# 02_MCU.net
KiCad netlist of a schematic drawn in Altium Designer
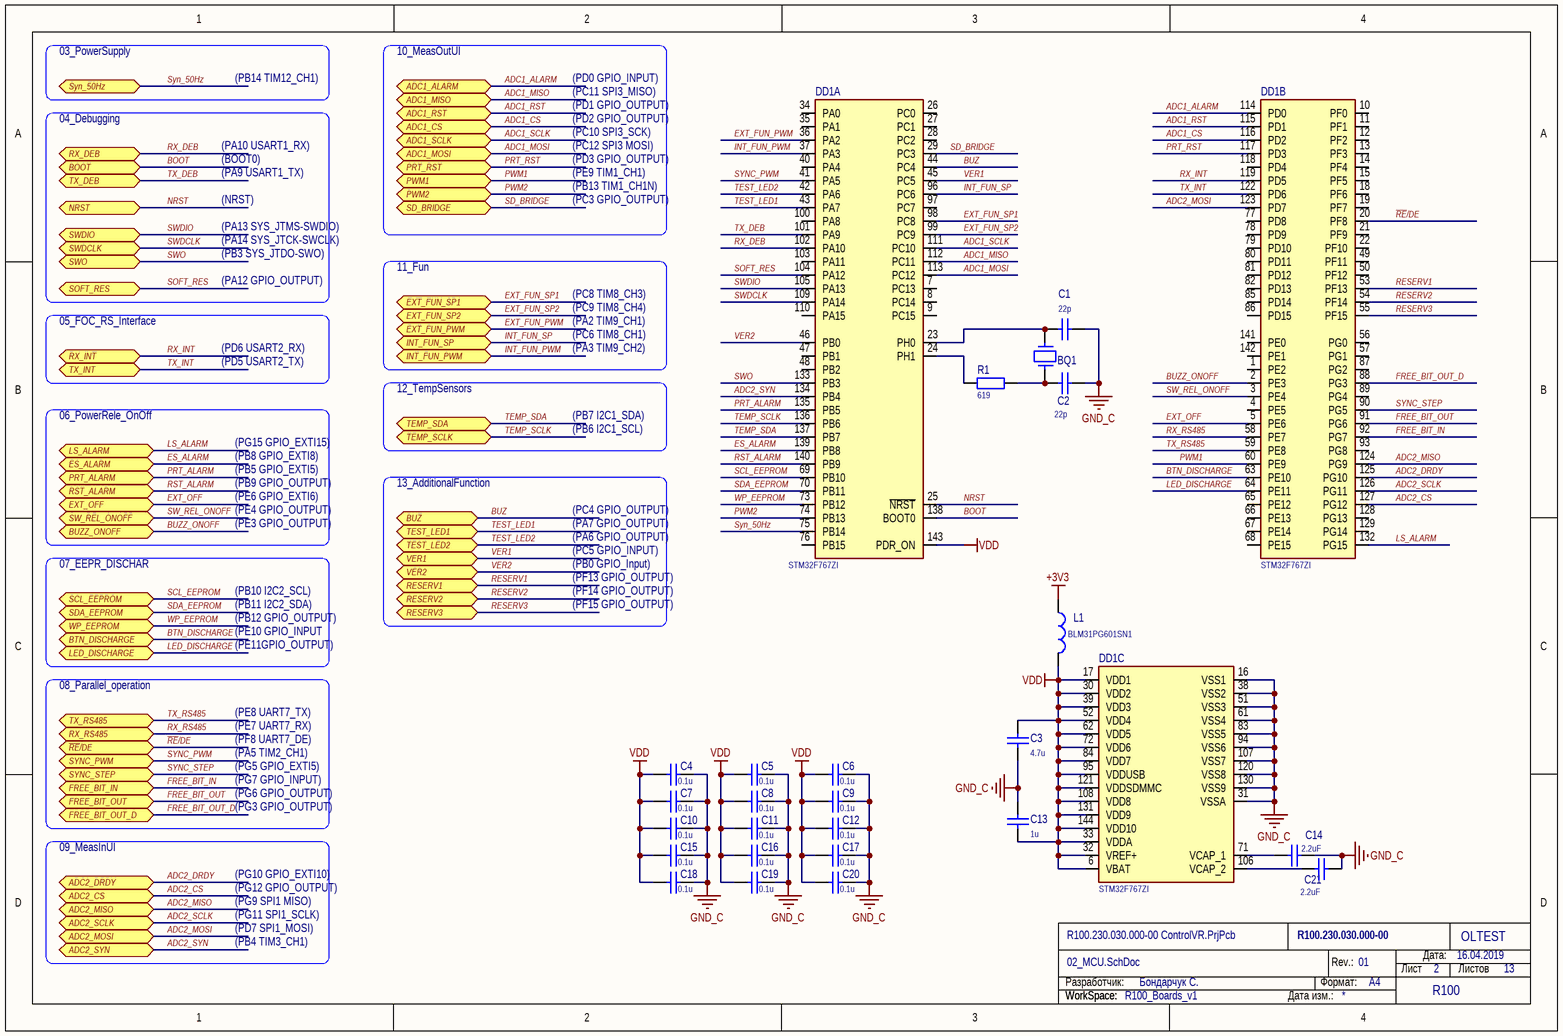
[diagram p0: 02_MCU.SchDoc]

(export (version "E")
  (design (tool "Eeschema 10.0.6"))
  (components
    (comp (ref "BQ1")
      (value "12MHz")
      (footprint "mainLib:DFN390P500X135-2N")
      (description "12MHz Quartz Crystal 7A")
      (fields (field (name "PARTNUMBER") "7A-12.000MAAJ-T") (field (name "MANUFACTURER") "TXC"))
      (libsource (lib "mainLib") (part "7A-12.000MAAJ-T"))
    )
    (comp (ref "C1")
      (value "22р")
      (footprint "mainLib:SMD_C_0603")
      (description "SMD C 0603 MURATA 50V 5% C0G")
      (fields (field (name "PARTNUMBER") "GRM1885C1H220JA01") (field (name "MANUFACTURER") "MURATA"))
      (libsource (lib "mainRCLib") (part "C0603 22p 50V 5%"))
    )
    (comp (ref "C2")
      (value "22р")
      (footprint "mainLib:SMD_C_0603")
      (description "SMD C 0603 MURATA 50V 5% C0G")
      (fields (field (name "PARTNUMBER") "GRM1885C1H220JA01") (field (name "MANUFACTURER") "MURATA"))
      (libsource (lib "mainRCLib") (part "C0603 22p 50V 5%"))
    )
    (comp (ref "C3")
      (value "4.7u")
      (footprint "mainLib:SMD_C_0805")
      (description "SMD C 0805 MURATA 50V 5% NP0")
      (fields (field (name "PARTNUMBER") "GRM21BR61E475M") (field (name "MANUFACTURER") "MURATA"))
      (libsource (lib "mainRCLib") (part "C0805 4.7u 25V 20%  X5R"))
    )
    (comp (ref "C4")
      (value "0.1u")
      (footprint "mainLib:SMD_C_0603")
      (description "SMD C 0603 MURATA 50V 10% X7R")
      (fields (field (name "PARTNUMBER") "GRM188R71H104K") (field (name "MANUFACTURER") "MURATA"))
      (libsource (lib "mainRCLib") (part "C0603 0.1u 50V 10%"))
    )
    (comp (ref "C5")
      (value "0.1u")
      (footprint "mainLib:SMD_C_0603")
      (description "SMD C 0603 MURATA 50V 10% X7R")
      (fields (field (name "PARTNUMBER") "GRM188R71H104K") (field (name "MANUFACTURER") "MURATA"))
      (libsource (lib "mainRCLib") (part "C0603 0.1u 50V 10%"))
    )
    (comp (ref "C6")
      (value "0.1u")
      (footprint "mainLib:SMD_C_0603")
      (description "SMD C 0603 MURATA 50V 10% X7R")
      (fields (field (name "PARTNUMBER") "GRM188R71H104K") (field (name "MANUFACTURER") "MURATA"))
      (libsource (lib "mainRCLib") (part "C0603 0.1u 50V 10%"))
    )
    (comp (ref "C7")
      (value "0.1u")
      (footprint "mainLib:SMD_C_0603")
      (description "SMD C 0603 MURATA 50V 10% X7R")
      (fields (field (name "PARTNUMBER") "GRM188R71H104K") (field (name "MANUFACTURER") "MURATA"))
      (libsource (lib "mainRCLib") (part "C0603 0.1u 50V 10%"))
    )
    (comp (ref "C8")
      (value "0.1u")
      (footprint "mainLib:SMD_C_0603")
      (description "SMD C 0603 MURATA 50V 10% X7R")
      (fields (field (name "PARTNUMBER") "GRM188R71H104K") (field (name "MANUFACTURER") "MURATA"))
      (libsource (lib "mainRCLib") (part "C0603 0.1u 50V 10%"))
    )
    (comp (ref "C9")
      (value "0.1u")
      (footprint "mainLib:SMD_C_0603")
      (description "SMD C 0603 MURATA 50V 10% X7R")
      (fields (field (name "PARTNUMBER") "GRM188R71H104K") (field (name "MANUFACTURER") "MURATA"))
      (libsource (lib "mainRCLib") (part "C0603 0.1u 50V 10%"))
    )
    (comp (ref "C10")
      (value "0.1u")
      (footprint "mainLib:SMD_C_0603")
      (description "SMD C 0603 MURATA 50V 10% X7R")
      (fields (field (name "PARTNUMBER") "GRM188R71H104K") (field (name "MANUFACTURER") "MURATA"))
      (libsource (lib "mainRCLib") (part "C0603 0.1u 50V 10%"))
    )
    (comp (ref "C11")
      (value "0.1u")
      (footprint "mainLib:SMD_C_0603")
      (description "SMD C 0603 MURATA 50V 10% X7R")
      (fields (field (name "PARTNUMBER") "GRM188R71H104K") (field (name "MANUFACTURER") "MURATA"))
      (libsource (lib "mainRCLib") (part "C0603 0.1u 50V 10%"))
    )
    (comp (ref "C12")
      (value "0.1u")
      (footprint "mainLib:SMD_C_0603")
      (description "SMD C 0603 MURATA 50V 10% X7R")
      (fields (field (name "PARTNUMBER") "GRM188R71H104K") (field (name "MANUFACTURER") "MURATA"))
      (libsource (lib "mainRCLib") (part "C0603 0.1u 50V 10%"))
    )
    (comp (ref "C13")
      (value "1u")
      (footprint "mainLib:SMD_C_0603")
      (description "SMD C 0603 MURATA 25V 10% X7R")
      (fields (field (name "PARTNUMBER") "GRM188R71E105KA12") (field (name "MANUFACTURER") "MURATA"))
      (libsource (lib "mainRCLib") (part "C0603 1uF 25V 10%"))
    )
    (comp (ref "C14")
      (value "2.2uF")
      (footprint "mainLib:SMD_C_0805")
      (description "SMD C 0805 MURATA 25V 10% X7R")
      (fields (field (name "PARTNUMBER") "GRM21BR61H225M") (field (name "MANUFACTURER") "MURATA"))
      (libsource (lib "mainRCLib") (part "C0805 2.2u 25V 10% X7R"))
    )
    (comp (ref "C15")
      (value "0.1u")
      (footprint "mainLib:SMD_C_0603")
      (description "SMD C 0603 MURATA 50V 10% X7R")
      (fields (field (name "PARTNUMBER") "GRM188R71H104K") (field (name "MANUFACTURER") "MURATA"))
      (libsource (lib "mainRCLib") (part "C0603 0.1u 50V 10%"))
    )
    (comp (ref "C16")
      (value "0.1u")
      (footprint "mainLib:SMD_C_0603")
      (description "SMD C 0603 MURATA 50V 10% X7R")
      (fields (field (name "PARTNUMBER") "GRM188R71H104K") (field (name "MANUFACTURER") "MURATA"))
      (libsource (lib "mainRCLib") (part "C0603 0.1u 50V 10%"))
    )
    (comp (ref "C17")
      (value "0.1u")
      (footprint "mainLib:SMD_C_0603")
      (description "SMD C 0603 MURATA 50V 10% X7R")
      (fields (field (name "PARTNUMBER") "GRM188R71H104K") (field (name "MANUFACTURER") "MURATA"))
      (libsource (lib "mainRCLib") (part "C0603 0.1u 50V 10%"))
    )
    (comp (ref "C18")
      (value "0.1u")
      (footprint "mainLib:SMD_C_0603")
      (description "SMD C 0603 MURATA 50V 10% X7R")
      (fields (field (name "PARTNUMBER") "GRM188R71H104K") (field (name "MANUFACTURER") "MURATA"))
      (libsource (lib "mainRCLib") (part "C0603 0.1u 50V 10%"))
    )
    (comp (ref "C19")
      (value "0.1u")
      (footprint "mainLib:SMD_C_0603")
      (description "SMD C 0603 MURATA 50V 10% X7R")
      (fields (field (name "PARTNUMBER") "GRM188R71H104K") (field (name "MANUFACTURER") "MURATA"))
      (libsource (lib "mainRCLib") (part "C0603 0.1u 50V 10%"))
    )
    (comp (ref "C20")
      (value "0.1u")
      (footprint "mainLib:SMD_C_0603")
      (description "SMD C 0603 MURATA 50V 10% X7R")
      (fields (field (name "PARTNUMBER") "GRM188R71H104K") (field (name "MANUFACTURER") "MURATA"))
      (libsource (lib "mainRCLib") (part "C0603 0.1u 50V 10%"))
    )
    (comp (ref "C21")
      (value "2.2uF")
      (footprint "mainLib:SMD_C_0805")
      (description "SMD C 0805 MURATA 25V 10% X7R")
      (fields (field (name "PARTNUMBER") "GRM21BR61H225M") (field (name "MANUFACTURER") "MURATA"))
      (libsource (lib "mainRCLib") (part "C0805 2.2u 25V 10% X7R"))
    )
    (comp (ref "DD1")
      (value "STM32F767ZI")
      (footprint "mainLib:SOT486-1_V")
      (description "32-bit ARM Cortex-M7 MCU+FPU")
      (libsource (lib "mainLib") (part "STM32F767ZI"))
    )
    (comp (ref "L1")
      (value "BLM31PG601SN1")
      (footprint "mainLib:SMD_L_1206")
      (description "600R 1.5A (100MHz)")
      (fields (field (name "MANUFACTURER") "TDK"))
      (libsource (lib "mainLib") (part "BLM31PG601SN1"))
    )
    (comp (ref "R1")
      (value "619")
      (footprint "mainLib:SMD_R_0603")
      (description "SMD 0603 VISHAY 0.1W 75V 1% 100ppm")
      (fields (field (name "PARTNUMBER") "CRCW0603619RFK") (field (name "MANUFACTURER") "VISHAY"))
      (libsource (lib "mainRCLib") (part "R0603 619 1%"))
    )
  )
  (nets
    (net (code "1") (name "+3V3") (class "Default")
      (node (ref "L1") (pin "1") (pinfunction "1_1") (pintype "passive"))
    )
    (net (code "2") (name "/ADC1_ALARM") (class "Default")
      (node (ref "DD1") (pin "114") (pinfunction "PD0_114") (pintype "passive"))
    )
    (net (code "3") (name "/ADC1_CS") (class "Default")
      (node (ref "DD1") (pin "116") (pinfunction "PD2_116") (pintype "passive"))
    )
    (net (code "4") (name "/ADC1_MISO") (class "Default")
      (node (ref "DD1") (pin "112") (pinfunction "PC11_112") (pintype "passive"))
    )
    (net (code "5") (name "/ADC1_MOSI") (class "Default")
      (node (ref "DD1") (pin "113") (pinfunction "PC12_113") (pintype "passive"))
    )
    (net (code "6") (name "/ADC1_RST") (class "Default")
      (node (ref "DD1") (pin "115") (pinfunction "PD1_115") (pintype "passive"))
    )
    (net (code "7") (name "/ADC1_SCLK") (class "Default")
      (node (ref "DD1") (pin "111") (pinfunction "PC10_111") (pintype "passive"))
    )
    (net (code "8") (name "/ADC2_CS") (class "Default")
      (node (ref "DD1") (pin "127") (pinfunction "PG12_127") (pintype "passive"))
    )
    (net (code "9") (name "/ADC2_DRDY") (class "Default")
      (node (ref "DD1") (pin "125") (pinfunction "PG10_125") (pintype "passive"))
    )
    (net (code "10") (name "/ADC2_MISO") (class "Default")
      (node (ref "DD1") (pin "124") (pinfunction "PG9_124") (pintype "passive"))
    )
    (net (code "11") (name "/ADC2_MOSI") (class "Default")
      (node (ref "DD1") (pin "123") (pinfunction "PD7_123") (pintype "passive"))
    )
    (net (code "12") (name "/ADC2_SCLK") (class "Default")
      (node (ref "DD1") (pin "126") (pinfunction "PG11_126") (pintype "passive"))
    )
    (net (code "13") (name "/ADC2_SYN") (class "Default")
      (node (ref "DD1") (pin "134") (pinfunction "PB4_134") (pintype "passive"))
    )
    (net (code "14") (name "/BOOT") (class "Default")
      (node (ref "DD1") (pin "138") (pinfunction "BOOT0_138") (pintype "passive"))
    )
    (net (code "15") (name "/BTN_DISCHARGE") (class "Default")
      (node (ref "DD1") (pin "63") (pinfunction "PE10_63") (pintype "passive"))
    )
    (net (code "16") (name "/BUZ") (class "Default")
      (node (ref "DD1") (pin "44") (pinfunction "PC4_44") (pintype "passive"))
    )
    (net (code "17") (name "/BUZZ_ONOFF") (class "Default")
      (node (ref "DD1") (pin "2") (pinfunction "PE3_2") (pintype "passive"))
    )
    (net (code "18") (name "/ES_ALARM") (class "Default")
      (node (ref "DD1") (pin "139") (pinfunction "PB8_139") (pintype "passive"))
    )
    (net (code "19") (name "/EXT_FUN_PWM") (class "Default")
      (node (ref "DD1") (pin "36") (pinfunction "PA2_36") (pintype "passive"))
    )
    (net (code "20") (name "/EXT_FUN_SP1") (class "Default")
      (node (ref "DD1") (pin "98") (pinfunction "PC8_98") (pintype "passive"))
    )
    (net (code "21") (name "/EXT_FUN_SP2") (class "Default")
      (node (ref "DD1") (pin "99") (pinfunction "PC9_99") (pintype "passive"))
    )
    (net (code "22") (name "/EXT_OFF") (class "Default")
      (node (ref "DD1") (pin "5") (pinfunction "PE6_5") (pintype "passive"))
    )
    (net (code "23") (name "/FREE_BIT_IN") (class "Default")
      (node (ref "DD1") (pin "92") (pinfunction "PG7_92") (pintype "passive"))
    )
    (net (code "24") (name "/FREE_BIT_OUT") (class "Default")
      (node (ref "DD1") (pin "91") (pinfunction "PG6_91") (pintype "passive"))
    )
    (net (code "25") (name "/FREE_BIT_OUT_D") (class "Default")
      (node (ref "DD1") (pin "88") (pinfunction "PG3_88") (pintype "passive"))
    )
    (net (code "26") (name "/INT_FUN_PWM") (class "Default")
      (node (ref "DD1") (pin "37") (pinfunction "PA3_37") (pintype "passive"))
    )
    (net (code "27") (name "/INT_FUN_SP") (class "Default")
      (node (ref "DD1") (pin "96") (pinfunction "PC6_96") (pintype "passive"))
    )
    (net (code "28") (name "/LED_DISCHARGE") (class "Default")
      (node (ref "DD1") (pin "64") (pinfunction "PE11_64") (pintype "passive"))
    )
    (net (code "29") (name "/LS_ALARM") (class "Default")
      (node (ref "DD1") (pin "132") (pinfunction "PG15_132") (pintype "passive"))
    )
    (net (code "30") (name "/NRST") (class "Default")
      (node (ref "DD1") (pin "25") (pinfunction "~{NRST}_25") (pintype "passive"))
    )
    (net (code "31") (name "/PRT_ALARM") (class "Default")
      (node (ref "DD1") (pin "135") (pinfunction "PB5_135") (pintype "passive"))
    )
    (net (code "32") (name "/PRT_RST") (class "Default")
      (node (ref "DD1") (pin "117") (pinfunction "PD3_117") (pintype "passive"))
    )
    (net (code "33") (name "/PWM1") (class "Default")
      (node (ref "DD1") (pin "60") (pinfunction "PE9_60") (pintype "passive"))
    )
    (net (code "34") (name "/PWM2") (class "Default")
      (node (ref "DD1") (pin "74") (pinfunction "PB13_74") (pintype "passive"))
    )
    (net (code "35") (name "/RESERV1") (class "Default")
      (node (ref "DD1") (pin "53") (pinfunction "PF13_53") (pintype "passive"))
    )
    (net (code "36") (name "/RESERV2") (class "Default")
      (node (ref "DD1") (pin "54") (pinfunction "PF14_54") (pintype "passive"))
    )
    (net (code "37") (name "/RESERV3") (class "Default")
      (node (ref "DD1") (pin "55") (pinfunction "PF15_55") (pintype "passive"))
    )
    (net (code "38") (name "/RST_ALARM") (class "Default")
      (node (ref "DD1") (pin "140") (pinfunction "PB9_140") (pintype "passive"))
    )
    (net (code "39") (name "/RX_DEB") (class "Default")
      (node (ref "DD1") (pin "102") (pinfunction "PA10_102") (pintype "passive"))
    )
    (net (code "40") (name "/RX_INT") (class "Default")
      (node (ref "DD1") (pin "119") (pinfunction "PD5_119") (pintype "passive"))
    )
    (net (code "41") (name "/RX_RS485") (class "Default")
      (node (ref "DD1") (pin "58") (pinfunction "PE7_58") (pintype "passive"))
    )
    (net (code "42") (name "/SCL_EEPROM") (class "Default")
      (node (ref "DD1") (pin "69") (pinfunction "PB10_69") (pintype "passive"))
    )
    (net (code "43") (name "/SDA_EEPROM") (class "Default")
      (node (ref "DD1") (pin "70") (pinfunction "PB11_70") (pintype "passive"))
    )
    (net (code "44") (name "/SD_BRIDGE") (class "Default")
      (node (ref "DD1") (pin "29") (pinfunction "PC3_29") (pintype "passive"))
    )
    (net (code "45") (name "/SOFT_RES") (class "Default")
      (node (ref "DD1") (pin "104") (pinfunction "PA12_104") (pintype "passive"))
    )
    (net (code "46") (name "/SWDCLK") (class "Default")
      (node (ref "DD1") (pin "109") (pinfunction "PA14_109") (pintype "passive"))
    )
    (net (code "47") (name "/SWDIO") (class "Default")
      (node (ref "DD1") (pin "105") (pinfunction "PA13_105") (pintype "passive"))
    )
    (net (code "48") (name "/SWO") (class "Default")
      (node (ref "DD1") (pin "133") (pinfunction "PB3_133") (pintype "passive"))
    )
    (net (code "49") (name "/SW_REL_ONOFF") (class "Default")
      (node (ref "DD1") (pin "3") (pinfunction "PE4_3") (pintype "passive"))
    )
    (net (code "50") (name "/SYNC_PWM") (class "Default")
      (node (ref "DD1") (pin "41") (pinfunction "PA5_41") (pintype "passive"))
    )
    (net (code "51") (name "/SYNC_STEP") (class "Default")
      (node (ref "DD1") (pin "90") (pinfunction "PG5_90") (pintype "passive"))
    )
    (net (code "52") (name "/Syn_50Hz") (class "Default")
      (node (ref "DD1") (pin "75") (pinfunction "PB14_75") (pintype "passive"))
    )
    (net (code "53") (name "/TEMP_SCLK") (class "Default")
      (node (ref "DD1") (pin "136") (pinfunction "PB6_136") (pintype "passive"))
    )
    (net (code "54") (name "/TEMP_SDA") (class "Default")
      (node (ref "DD1") (pin "137") (pinfunction "PB7_137") (pintype "passive"))
    )
    (net (code "55") (name "/TEST_LED1") (class "Default")
      (node (ref "DD1") (pin "43") (pinfunction "PA7_43") (pintype "passive"))
    )
    (net (code "56") (name "/TEST_LED2") (class "Default")
      (node (ref "DD1") (pin "42") (pinfunction "PA6_42") (pintype "passive"))
    )
    (net (code "57") (name "/TX_DEB") (class "Default")
      (node (ref "DD1") (pin "101") (pinfunction "PA9_101") (pintype "passive"))
    )
    (net (code "58") (name "/TX_INT") (class "Default")
      (node (ref "DD1") (pin "122") (pinfunction "PD6_122") (pintype "passive"))
    )
    (net (code "59") (name "/TX_RS485") (class "Default")
      (node (ref "DD1") (pin "59") (pinfunction "PE8_59") (pintype "passive"))
    )
    (net (code "60") (name "/VER1") (class "Default")
      (node (ref "DD1") (pin "45") (pinfunction "PC5_45") (pintype "passive"))
    )
    (net (code "61") (name "/VER2") (class "Default")
      (node (ref "DD1") (pin "46") (pinfunction "PB0_46") (pintype "passive"))
    )
    (net (code "62") (name "/WP_EEPROM") (class "Default")
      (node (ref "DD1") (pin "73") (pinfunction "PB12_73") (pintype "passive"))
    )
    (net (code "63") (name "/~{RE}{slash}DE") (class "Default")
      (node (ref "DD1") (pin "20") (pinfunction "PF8_20") (pintype "passive"))
    )
    (net (code "64") (name "GND_C") (class "Default")
      (node (ref "C1") (pin "2") (pinfunction "2_2") (pintype "passive"))
      (node (ref "C10") (pin "2") (pinfunction "2_2") (pintype "passive"))
      (node (ref "C11") (pin "2") (pinfunction "2_2") (pintype "passive"))
      (node (ref "C12") (pin "2") (pinfunction "2_2") (pintype "passive"))
      (node (ref "C13") (pin "2") (pinfunction "2_2") (pintype "passive"))
      (node (ref "C14") (pin "2") (pinfunction "2_2") (pintype "passive"))
      (node (ref "C15") (pin "2") (pinfunction "2_2") (pintype "passive"))
      (node (ref "C16") (pin "2") (pinfunction "2_2") (pintype "passive"))
      (node (ref "C17") (pin "2") (pinfunction "2_2") (pintype "passive"))
      (node (ref "C18") (pin "2") (pinfunction "2_2") (pintype "passive"))
      (node (ref "C19") (pin "2") (pinfunction "2_2") (pintype "passive"))
      (node (ref "C2") (pin "2") (pinfunction "2_2") (pintype "passive"))
      (node (ref "C20") (pin "2") (pinfunction "2_2") (pintype "passive"))
      (node (ref "C21") (pin "2") (pinfunction "2_2") (pintype "passive"))
      (node (ref "C3") (pin "1") (pinfunction "1_1") (pintype "passive"))
      (node (ref "C4") (pin "2") (pinfunction "2_2") (pintype "passive"))
      (node (ref "C5") (pin "2") (pinfunction "2_2") (pintype "passive"))
      (node (ref "C6") (pin "2") (pinfunction "2_2") (pintype "passive"))
      (node (ref "C7") (pin "2") (pinfunction "2_2") (pintype "passive"))
      (node (ref "C8") (pin "2") (pinfunction "2_2") (pintype "passive"))
      (node (ref "C9") (pin "2") (pinfunction "2_2") (pintype "passive"))
      (node (ref "DD1") (pin "107") (pinfunction "VSS7_107") (pintype "passive"))
      (node (ref "DD1") (pin "120") (pinfunction "VSS8_120") (pintype "passive"))
      (node (ref "DD1") (pin "130") (pinfunction "VSS9_130") (pintype "passive"))
      (node (ref "DD1") (pin "16") (pinfunction "VSS1_16") (pintype "passive"))
      (node (ref "DD1") (pin "31") (pinfunction "VSSA_31") (pintype "passive"))
      (node (ref "DD1") (pin "38") (pinfunction "VSS2_38") (pintype "passive"))
      (node (ref "DD1") (pin "51") (pinfunction "VSS3_51") (pintype "passive"))
      (node (ref "DD1") (pin "61") (pinfunction "VSS4_61") (pintype "passive"))
      (node (ref "DD1") (pin "83") (pinfunction "VSS5_83") (pintype "passive"))
      (node (ref "DD1") (pin "94") (pinfunction "VSS6_94") (pintype "passive"))
    )
    (net (code "65") (name "Net-(BQ1-Pad1)") (class "Default")
      (node (ref "BQ1") (pin "1") (pinfunction "1_1") (pintype "passive"))
      (node (ref "C2") (pin "1") (pinfunction "1_1") (pintype "passive"))
      (node (ref "R1") (pin "2") (pinfunction "2_2") (pintype "passive"))
    )
    (net (code "66") (name "Net-(DD1A-PH0)") (class "Default")
      (node (ref "BQ1") (pin "2") (pinfunction "2_2") (pintype "passive"))
      (node (ref "C1") (pin "1") (pinfunction "1_1") (pintype "passive"))
      (node (ref "DD1") (pin "23") (pinfunction "PH0_23") (pintype "passive"))
    )
    (net (code "67") (name "Net-(DD1A-PH1)") (class "Default")
      (node (ref "DD1") (pin "24") (pinfunction "PH1_24") (pintype "passive"))
      (node (ref "R1") (pin "1") (pinfunction "1_1") (pintype "passive"))
    )
    (net (code "68") (name "Net-(DD1C-VCAP_1)") (class "Default")
      (node (ref "C14") (pin "1") (pinfunction "1_1") (pintype "passive"))
      (node (ref "DD1") (pin "71") (pinfunction "VCAP_1_71") (pintype "passive"))
    )
    (net (code "69") (name "Net-(DD1C-VCAP_2)") (class "Default")
      (node (ref "C21") (pin "1") (pinfunction "1_1") (pintype "passive"))
      (node (ref "DD1") (pin "106") (pinfunction "VCAP_2_106") (pintype "passive"))
    )
    (net (code "70") (name "VDD") (class "Default")
      (node (ref "C10") (pin "1") (pinfunction "1_1") (pintype "passive"))
      (node (ref "C11") (pin "1") (pinfunction "1_1") (pintype "passive"))
      (node (ref "C12") (pin "1") (pinfunction "1_1") (pintype "passive"))
      (node (ref "C13") (pin "1") (pinfunction "1_1") (pintype "passive"))
      (node (ref "C15") (pin "1") (pinfunction "1_1") (pintype "passive"))
      (node (ref "C16") (pin "1") (pinfunction "1_1") (pintype "passive"))
      (node (ref "C17") (pin "1") (pinfunction "1_1") (pintype "passive"))
      (node (ref "C18") (pin "1") (pinfunction "1_1") (pintype "passive"))
      (node (ref "C19") (pin "1") (pinfunction "1_1") (pintype "passive"))
      (node (ref "C20") (pin "1") (pinfunction "1_1") (pintype "passive"))
      (node (ref "C3") (pin "2") (pinfunction "2_2") (pintype "passive"))
      (node (ref "C4") (pin "1") (pinfunction "1_1") (pintype "passive"))
      (node (ref "C5") (pin "1") (pinfunction "1_1") (pintype "passive"))
      (node (ref "C6") (pin "1") (pinfunction "1_1") (pintype "passive"))
      (node (ref "C7") (pin "1") (pinfunction "1_1") (pintype "passive"))
      (node (ref "C8") (pin "1") (pinfunction "1_1") (pintype "passive"))
      (node (ref "C9") (pin "1") (pinfunction "1_1") (pintype "passive"))
      (node (ref "DD1") (pin "108") (pinfunction "VDD8_108") (pintype "passive"))
      (node (ref "DD1") (pin "121") (pinfunction "VDDSDMMC_121") (pintype "passive"))
      (node (ref "DD1") (pin "131") (pinfunction "VDD9_131") (pintype "passive"))
      (node (ref "DD1") (pin "143") (pinfunction "PDR_ON_143") (pintype "passive"))
      (node (ref "DD1") (pin "144") (pinfunction "VDD10_144") (pintype "passive"))
      (node (ref "DD1") (pin "17") (pinfunction "VDD1_17") (pintype "passive"))
      (node (ref "DD1") (pin "30") (pinfunction "VDD2_30") (pintype "passive"))
      (node (ref "DD1") (pin "32") (pinfunction "VREF+_32") (pintype "passive"))
      (node (ref "DD1") (pin "33") (pinfunction "VDDA_33") (pintype "passive"))
      (node (ref "DD1") (pin "39") (pinfunction "VDD3_39") (pintype "passive"))
      (node (ref "DD1") (pin "52") (pinfunction "VDD4_52") (pintype "passive"))
      (node (ref "DD1") (pin "6") (pinfunction "VBAT_6") (pintype "passive"))
      (node (ref "DD1") (pin "62") (pinfunction "VDD5_62") (pintype "passive"))
      (node (ref "DD1") (pin "72") (pinfunction "VDD6_72") (pintype "passive"))
      (node (ref "DD1") (pin "84") (pinfunction "VDD7_84") (pintype "passive"))
      (node (ref "DD1") (pin "95") (pinfunction "VDDUSB_95") (pintype "passive"))
      (node (ref "L1") (pin "2") (pinfunction "2_2") (pintype "passive"))
    )
    (net (code "71") (name "unconnected-(DD1A-PA0-Pad34)") (class "Default")
      (node (ref "DD1") (pin "34") (pinfunction "PA0_34") (pintype "passive"))
    )
    (net (code "72") (name "unconnected-(DD1A-PA1-Pad35)") (class "Default")
      (node (ref "DD1") (pin "35") (pinfunction "PA1_35") (pintype "passive"))
    )
    (net (code "73") (name "unconnected-(DD1A-PA4-Pad40)") (class "Default")
      (node (ref "DD1") (pin "40") (pinfunction "PA4_40") (pintype "passive"))
    )
    (net (code "74") (name "unconnected-(DD1A-PA8-Pad100)") (class "Default")
      (node (ref "DD1") (pin "100") (pinfunction "PA8_100") (pintype "passive"))
    )
    (net (code "75") (name "unconnected-(DD1A-PA11-Pad103)") (class "Default")
      (node (ref "DD1") (pin "103") (pinfunction "PA11_103") (pintype "passive"))
    )
    (net (code "76") (name "unconnected-(DD1A-PA15-Pad110)") (class "Default")
      (node (ref "DD1") (pin "110") (pinfunction "PA15_110") (pintype "passive"))
    )
    (net (code "77") (name "unconnected-(DD1A-PB1-Pad47)") (class "Default")
      (node (ref "DD1") (pin "47") (pinfunction "PB1_47") (pintype "passive"))
    )
    (net (code "78") (name "unconnected-(DD1A-PB2-Pad48)") (class "Default")
      (node (ref "DD1") (pin "48") (pinfunction "PB2_48") (pintype "passive"))
    )
    (net (code "79") (name "unconnected-(DD1A-PB15-Pad76)") (class "Default")
      (node (ref "DD1") (pin "76") (pinfunction "PB15_76") (pintype "passive"))
    )
    (net (code "80") (name "unconnected-(DD1A-PC0-Pad26)") (class "Default")
      (node (ref "DD1") (pin "26") (pinfunction "PC0_26") (pintype "passive"))
    )
    (net (code "81") (name "unconnected-(DD1A-PC1-Pad27)") (class "Default")
      (node (ref "DD1") (pin "27") (pinfunction "PC1_27") (pintype "passive"))
    )
    (net (code "82") (name "unconnected-(DD1A-PC2-Pad28)") (class "Default")
      (node (ref "DD1") (pin "28") (pinfunction "PC2_28") (pintype "passive"))
    )
    (net (code "83") (name "unconnected-(DD1A-PC7-Pad97)") (class "Default")
      (node (ref "DD1") (pin "97") (pinfunction "PC7_97") (pintype "passive"))
    )
    (net (code "84") (name "unconnected-(DD1A-PC13-Pad7)") (class "Default")
      (node (ref "DD1") (pin "7") (pinfunction "PC13_7") (pintype "passive"))
    )
    (net (code "85") (name "unconnected-(DD1A-PC14-Pad8)") (class "Default")
      (node (ref "DD1") (pin "8") (pinfunction "PC14_8") (pintype "passive"))
    )
    (net (code "86") (name "unconnected-(DD1A-PC15-Pad9)") (class "Default")
      (node (ref "DD1") (pin "9") (pinfunction "PC15_9") (pintype "passive"))
    )
    (net (code "87") (name "unconnected-(DD1B-PD4-Pad118)") (class "Default")
      (node (ref "DD1") (pin "118") (pinfunction "PD4_118") (pintype "passive"))
    )
    (net (code "88") (name "unconnected-(DD1B-PD8-Pad77)") (class "Default")
      (node (ref "DD1") (pin "77") (pinfunction "PD8_77") (pintype "passive"))
    )
    (net (code "89") (name "unconnected-(DD1B-PD9-Pad78)") (class "Default")
      (node (ref "DD1") (pin "78") (pinfunction "PD9_78") (pintype "passive"))
    )
    (net (code "90") (name "unconnected-(DD1B-PD10-Pad79)") (class "Default")
      (node (ref "DD1") (pin "79") (pinfunction "PD10_79") (pintype "passive"))
    )
    (net (code "91") (name "unconnected-(DD1B-PD11-Pad80)") (class "Default")
      (node (ref "DD1") (pin "80") (pinfunction "PD11_80") (pintype "passive"))
    )
    (net (code "92") (name "unconnected-(DD1B-PD12-Pad81)") (class "Default")
      (node (ref "DD1") (pin "81") (pinfunction "PD12_81") (pintype "passive"))
    )
    (net (code "93") (name "unconnected-(DD1B-PD13-Pad82)") (class "Default")
      (node (ref "DD1") (pin "82") (pinfunction "PD13_82") (pintype "passive"))
    )
    (net (code "94") (name "unconnected-(DD1B-PD14-Pad85)") (class "Default")
      (node (ref "DD1") (pin "85") (pinfunction "PD14_85") (pintype "passive"))
    )
    (net (code "95") (name "unconnected-(DD1B-PD15-Pad86)") (class "Default")
      (node (ref "DD1") (pin "86") (pinfunction "PD15_86") (pintype "passive"))
    )
    (net (code "96") (name "unconnected-(DD1B-PE0-Pad141)") (class "Default")
      (node (ref "DD1") (pin "141") (pinfunction "PE0_141") (pintype "passive"))
    )
    (net (code "97") (name "unconnected-(DD1B-PE1-Pad142)") (class "Default")
      (node (ref "DD1") (pin "142") (pinfunction "PE1_142") (pintype "passive"))
    )
    (net (code "98") (name "unconnected-(DD1B-PE2-Pad1)") (class "Default")
      (node (ref "DD1") (pin "1") (pinfunction "PE2_1") (pintype "passive"))
    )
    (net (code "99") (name "unconnected-(DD1B-PE5-Pad4)") (class "Default")
      (node (ref "DD1") (pin "4") (pinfunction "PE5_4") (pintype "passive"))
    )
    (net (code "100") (name "unconnected-(DD1B-PE12-Pad65)") (class "Default")
      (node (ref "DD1") (pin "65") (pinfunction "PE12_65") (pintype "passive"))
    )
    (net (code "101") (name "unconnected-(DD1B-PE13-Pad66)") (class "Default")
      (node (ref "DD1") (pin "66") (pinfunction "PE13_66") (pintype "passive"))
    )
    (net (code "102") (name "unconnected-(DD1B-PE14-Pad67)") (class "Default")
      (node (ref "DD1") (pin "67") (pinfunction "PE14_67") (pintype "passive"))
    )
    (net (code "103") (name "unconnected-(DD1B-PE15-Pad68)") (class "Default")
      (node (ref "DD1") (pin "68") (pinfunction "PE15_68") (pintype "passive"))
    )
    (net (code "104") (name "unconnected-(DD1B-PF0-Pad10)") (class "Default")
      (node (ref "DD1") (pin "10") (pinfunction "PF0_10") (pintype "passive"))
    )
    (net (code "105") (name "unconnected-(DD1B-PF1-Pad11)") (class "Default")
      (node (ref "DD1") (pin "11") (pinfunction "PF1_11") (pintype "passive"))
    )
    (net (code "106") (name "unconnected-(DD1B-PF2-Pad12)") (class "Default")
      (node (ref "DD1") (pin "12") (pinfunction "PF2_12") (pintype "passive"))
    )
    (net (code "107") (name "unconnected-(DD1B-PF3-Pad13)") (class "Default")
      (node (ref "DD1") (pin "13") (pinfunction "PF3_13") (pintype "passive"))
    )
    (net (code "108") (name "unconnected-(DD1B-PF4-Pad14)") (class "Default")
      (node (ref "DD1") (pin "14") (pinfunction "PF4_14") (pintype "passive"))
    )
    (net (code "109") (name "unconnected-(DD1B-PF5-Pad15)") (class "Default")
      (node (ref "DD1") (pin "15") (pinfunction "PF5_15") (pintype "passive"))
    )
    (net (code "110") (name "unconnected-(DD1B-PF6-Pad18)") (class "Default")
      (node (ref "DD1") (pin "18") (pinfunction "PF6_18") (pintype "passive"))
    )
    (net (code "111") (name "unconnected-(DD1B-PF7-Pad19)") (class "Default")
      (node (ref "DD1") (pin "19") (pinfunction "PF7_19") (pintype "passive"))
    )
    (net (code "112") (name "unconnected-(DD1B-PF9-Pad21)") (class "Default")
      (node (ref "DD1") (pin "21") (pinfunction "PF9_21") (pintype "passive"))
    )
    (net (code "113") (name "unconnected-(DD1B-PF10-Pad22)") (class "Default")
      (node (ref "DD1") (pin "22") (pinfunction "PF10_22") (pintype "passive"))
    )
    (net (code "114") (name "unconnected-(DD1B-PF11-Pad49)") (class "Default")
      (node (ref "DD1") (pin "49") (pinfunction "PF11_49") (pintype "passive"))
    )
    (net (code "115") (name "unconnected-(DD1B-PF12-Pad50)") (class "Default")
      (node (ref "DD1") (pin "50") (pinfunction "PF12_50") (pintype "passive"))
    )
    (net (code "116") (name "unconnected-(DD1B-PG0-Pad56)") (class "Default")
      (node (ref "DD1") (pin "56") (pinfunction "PG0_56") (pintype "passive"))
    )
    (net (code "117") (name "unconnected-(DD1B-PG1-Pad57)") (class "Default")
      (node (ref "DD1") (pin "57") (pinfunction "PG1_57") (pintype "passive"))
    )
    (net (code "118") (name "unconnected-(DD1B-PG2-Pad87)") (class "Default")
      (node (ref "DD1") (pin "87") (pinfunction "PG2_87") (pintype "passive"))
    )
    (net (code "119") (name "unconnected-(DD1B-PG4-Pad89)") (class "Default")
      (node (ref "DD1") (pin "89") (pinfunction "PG4_89") (pintype "passive"))
    )
    (net (code "120") (name "unconnected-(DD1B-PG8-Pad93)") (class "Default")
      (node (ref "DD1") (pin "93") (pinfunction "PG8_93") (pintype "passive"))
    )
    (net (code "121") (name "unconnected-(DD1B-PG13-Pad128)") (class "Default")
      (node (ref "DD1") (pin "128") (pinfunction "PG13_128") (pintype "passive"))
    )
    (net (code "122") (name "unconnected-(DD1B-PG14-Pad129)") (class "Default")
      (node (ref "DD1") (pin "129") (pinfunction "PG14_129") (pintype "passive"))
    )
  )
)
